# cap_pcb.net
KiCad netlist of a schematic drawn in EAGLE
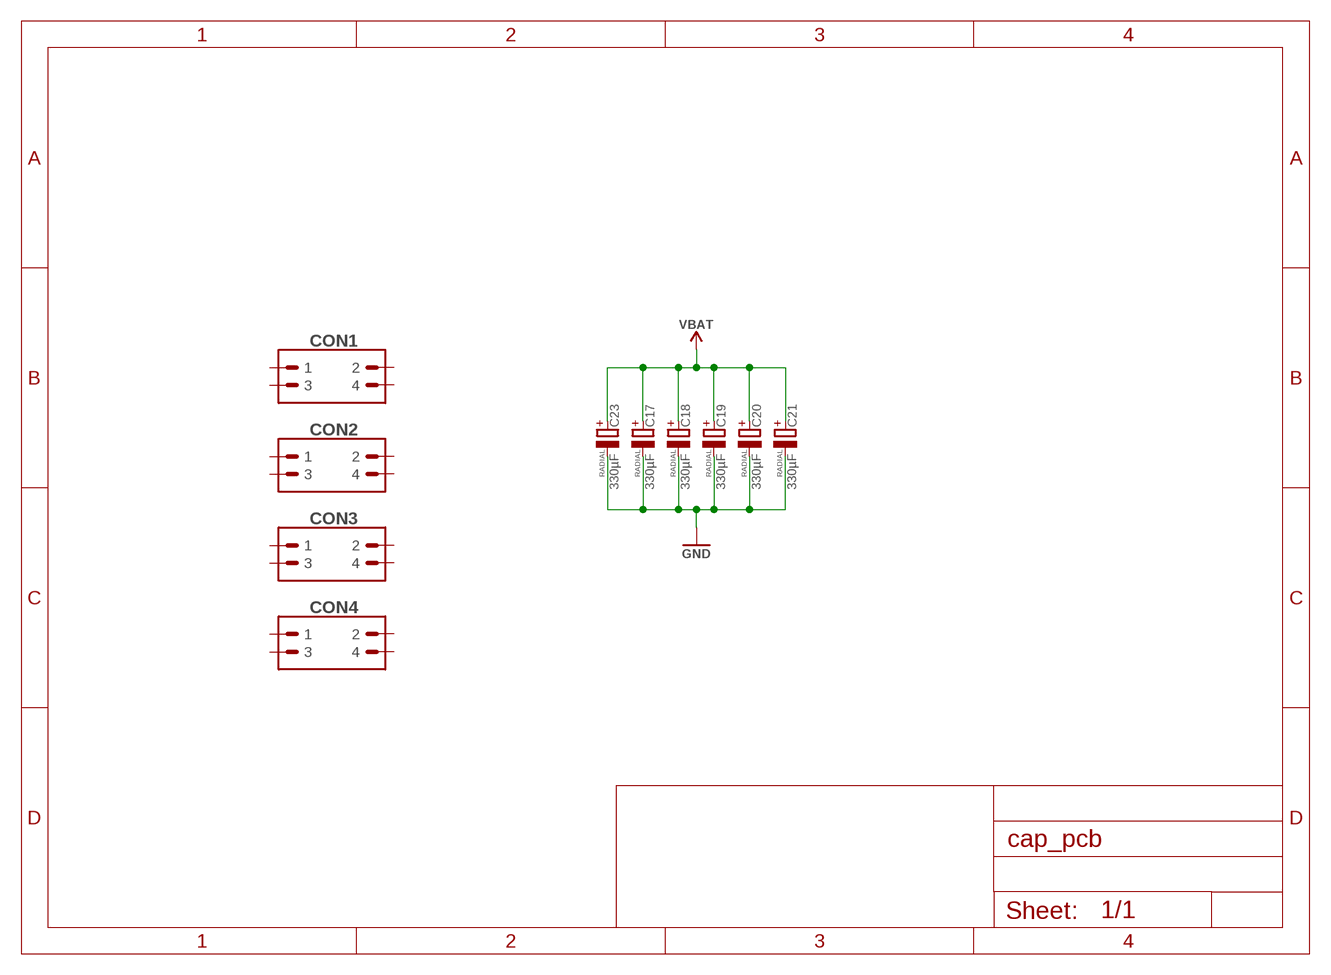
[diagram p0: schematic, sheet 1]

(export (version "E")
  (design (tool "Eeschema 10.0.6"))
  (components
    (comp (ref "C17")
      (value "330µF")
      (footprint "eagle-import:RADIAL_SIDE_12.5X22")
      (fields
        (field (name "PACKAGE") "RADIAL")
        (field (name "MANF") "EPCOS (TDK)")
        (field (name "VOLTAGE") "50V")
        (field (name "DIGIKEY#") "493-4784-3-ND")
        (field (name "MANF_1") "Nichicon")
        (field (name "MANF#") "UCY2C101MHD1TO")
        (field (name "VOLTAGE_1") "160V")
      )
      (libsource (lib "eagle-import") (part "CPOL-RADIAL_SIDE-12.5-22"))
    )
    (comp (ref "C18")
      (value "330µF")
      (footprint "eagle-import:RADIAL_SIDE_12.5X22")
      (fields
        (field (name "PACKAGE") "RADIAL")
        (field (name "MANF") "EPCOS (TDK)")
        (field (name "VOLTAGE") "50V")
        (field (name "DIGIKEY#") "493-4784-3-ND")
        (field (name "MANF_1") "Nichicon")
        (field (name "MANF#") "UCY2C101MHD1TO")
        (field (name "VOLTAGE_1") "160V")
      )
      (libsource (lib "eagle-import") (part "CPOL-RADIAL_SIDE-12.5-22"))
    )
    (comp (ref "C19")
      (value "330µF")
      (footprint "eagle-import:RADIAL_SIDE_12.5X22")
      (fields
        (field (name "PACKAGE") "RADIAL")
        (field (name "MANF") "EPCOS (TDK)")
        (field (name "VOLTAGE") "50V")
        (field (name "DIGIKEY#") "493-4784-3-ND")
        (field (name "MANF_1") "Nichicon")
        (field (name "MANF#") "UCY2C101MHD1TO")
        (field (name "VOLTAGE_1") "160V")
      )
      (libsource (lib "eagle-import") (part "CPOL-RADIAL_SIDE-12.5-22"))
    )
    (comp (ref "C20")
      (value "330µF")
      (footprint "eagle-import:RADIAL_SIDE_12.5X22")
      (fields
        (field (name "PACKAGE") "RADIAL")
        (field (name "MANF") "EPCOS (TDK)")
        (field (name "VOLTAGE") "50V")
        (field (name "DIGIKEY#") "493-4784-3-ND")
        (field (name "MANF_1") "Nichicon")
        (field (name "MANF#") "UCY2C101MHD1TO")
        (field (name "VOLTAGE_1") "160V")
      )
      (libsource (lib "eagle-import") (part "CPOL-RADIAL_SIDE-12.5-22"))
    )
    (comp (ref "C21")
      (value "330µF")
      (footprint "eagle-import:RADIAL_SIDE_12.5X22")
      (fields
        (field (name "PACKAGE") "RADIAL")
        (field (name "MANF") "EPCOS (TDK)")
        (field (name "VOLTAGE") "50V")
        (field (name "DIGIKEY#") "493-4784-3-ND")
        (field (name "MANF_1") "Nichicon")
        (field (name "MANF#") "UCY2C101MHD1TO")
        (field (name "VOLTAGE_1") "160V")
      )
      (libsource (lib "eagle-import") (part "CPOL-RADIAL_SIDE-12.5-22"))
    )
    (comp (ref "C23")
      (value "330µF")
      (footprint "eagle-import:RADIAL_SIDE_12.5X22")
      (fields
        (field (name "PACKAGE") "RADIAL")
        (field (name "MANF") "EPCOS (TDK)")
        (field (name "VOLTAGE") "50V")
        (field (name "DIGIKEY#") "493-4784-3-ND")
        (field (name "MANF_1") "Nichicon")
        (field (name "MANF#") "UCY2C101MHD1TO")
        (field (name "VOLTAGE_1") "160V")
      )
      (libsource (lib "eagle-import") (part "CPOL-RADIAL_SIDE-12.5-22"))
    )
    (comp (ref "CON1")
      (value "PINHEAD_2X02-PTH-2-MALE")
      (footprint "eagle-import:2X02-PTH-2")
      (libsource (lib "eagle-import") (part "PINHEAD_2X02-PTH-2-MALE"))
    )
    (comp (ref "CON2")
      (value "PINHEAD_2X02-PTH-2-MALE")
      (footprint "eagle-import:2X02-PTH-2")
      (libsource (lib "eagle-import") (part "PINHEAD_2X02-PTH-2-MALE"))
    )
    (comp (ref "CON3")
      (value "PINHEAD_2X02-PTH-2-MALE")
      (footprint "eagle-import:2X02-PTH-2")
      (libsource (lib "eagle-import") (part "PINHEAD_2X02-PTH-2-MALE"))
    )
    (comp (ref "CON4")
      (value "PINHEAD_2X02-PTH-2-MALE")
      (footprint "eagle-import:2X02-PTH-2")
      (libsource (lib "eagle-import") (part "PINHEAD_2X02-PTH-2-MALE"))
    )
  )
  (nets
    (net (code "1") (name "GND") (class "Default")
      (node (ref "C17") (pin "-") (pinfunction "-_-") (pintype "passive"))
      (node (ref "C18") (pin "-") (pinfunction "-_-") (pintype "passive"))
      (node (ref "C19") (pin "-") (pinfunction "-_-") (pintype "passive"))
      (node (ref "C20") (pin "-") (pinfunction "-_-") (pintype "passive"))
      (node (ref "C21") (pin "-") (pinfunction "-_-") (pintype "passive"))
      (node (ref "C23") (pin "-") (pinfunction "-_-") (pintype "passive"))
    )
    (net (code "2") (name "VBAT") (class "Default")
      (node (ref "C17") (pin "+") (pinfunction "+_+") (pintype "passive"))
      (node (ref "C18") (pin "+") (pinfunction "+_+") (pintype "passive"))
      (node (ref "C19") (pin "+") (pinfunction "+_+") (pintype "passive"))
      (node (ref "C20") (pin "+") (pinfunction "+_+") (pintype "passive"))
      (node (ref "C21") (pin "+") (pinfunction "+_+") (pintype "passive"))
      (node (ref "C23") (pin "+") (pinfunction "+_+") (pintype "passive"))
    )
    (net (code "3") (name "unconnected-(CON1-Pad1)") (class "Default")
      (node (ref "CON1") (pin "1") (pinfunction "1_1") (pintype "passive"))
    )
    (net (code "4") (name "unconnected-(CON1-Pad2)") (class "Default")
      (node (ref "CON1") (pin "2") (pinfunction "2_2") (pintype "passive"))
    )
    (net (code "5") (name "unconnected-(CON1-Pad3)") (class "Default")
      (node (ref "CON1") (pin "3") (pinfunction "3_3") (pintype "passive"))
    )
    (net (code "6") (name "unconnected-(CON1-Pad4)") (class "Default")
      (node (ref "CON1") (pin "4") (pinfunction "4_4") (pintype "passive"))
    )
    (net (code "7") (name "unconnected-(CON2-Pad1)") (class "Default")
      (node (ref "CON2") (pin "1") (pinfunction "1_1") (pintype "passive"))
    )
    (net (code "8") (name "unconnected-(CON2-Pad2)") (class "Default")
      (node (ref "CON2") (pin "2") (pinfunction "2_2") (pintype "passive"))
    )
    (net (code "9") (name "unconnected-(CON2-Pad3)") (class "Default")
      (node (ref "CON2") (pin "3") (pinfunction "3_3") (pintype "passive"))
    )
    (net (code "10") (name "unconnected-(CON2-Pad4)") (class "Default")
      (node (ref "CON2") (pin "4") (pinfunction "4_4") (pintype "passive"))
    )
    (net (code "11") (name "unconnected-(CON3-Pad1)") (class "Default")
      (node (ref "CON3") (pin "1") (pinfunction "1_1") (pintype "passive"))
    )
    (net (code "12") (name "unconnected-(CON3-Pad2)") (class "Default")
      (node (ref "CON3") (pin "2") (pinfunction "2_2") (pintype "passive"))
    )
    (net (code "13") (name "unconnected-(CON3-Pad3)") (class "Default")
      (node (ref "CON3") (pin "3") (pinfunction "3_3") (pintype "passive"))
    )
    (net (code "14") (name "unconnected-(CON3-Pad4)") (class "Default")
      (node (ref "CON3") (pin "4") (pinfunction "4_4") (pintype "passive"))
    )
    (net (code "15") (name "unconnected-(CON4-Pad1)") (class "Default")
      (node (ref "CON4") (pin "1") (pinfunction "1_1") (pintype "passive"))
    )
    (net (code "16") (name "unconnected-(CON4-Pad2)") (class "Default")
      (node (ref "CON4") (pin "2") (pinfunction "2_2") (pintype "passive"))
    )
    (net (code "17") (name "unconnected-(CON4-Pad3)") (class "Default")
      (node (ref "CON4") (pin "3") (pinfunction "3_3") (pintype "passive"))
    )
    (net (code "18") (name "unconnected-(CON4-Pad4)") (class "Default")
      (node (ref "CON4") (pin "4") (pinfunction "4_4") (pintype "passive"))
    )
  )
)
